# iot1.net
KiCad netlist of a schematic drawn in EAGLE
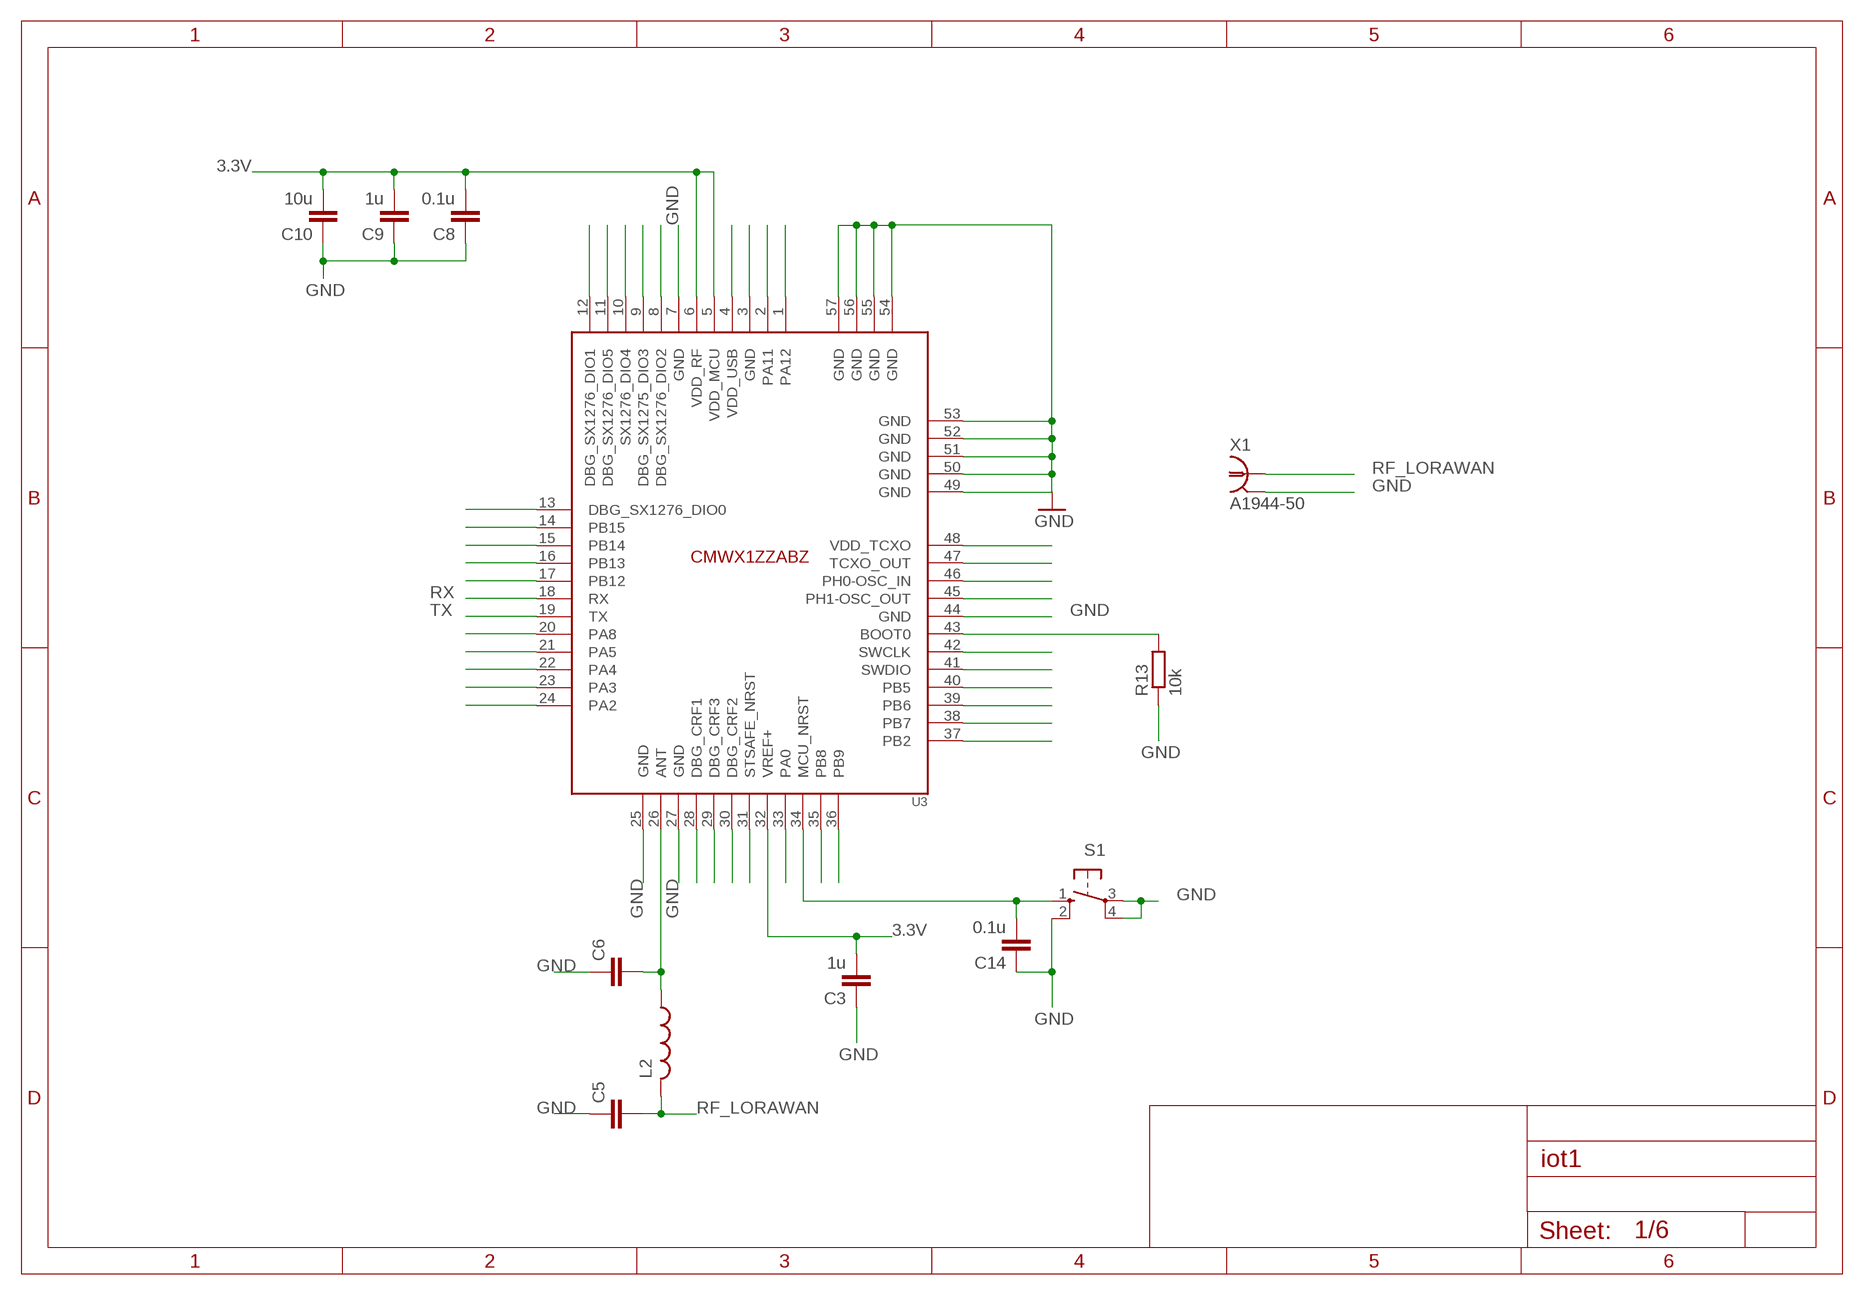
[diagram p0: schematic, sheet 1]
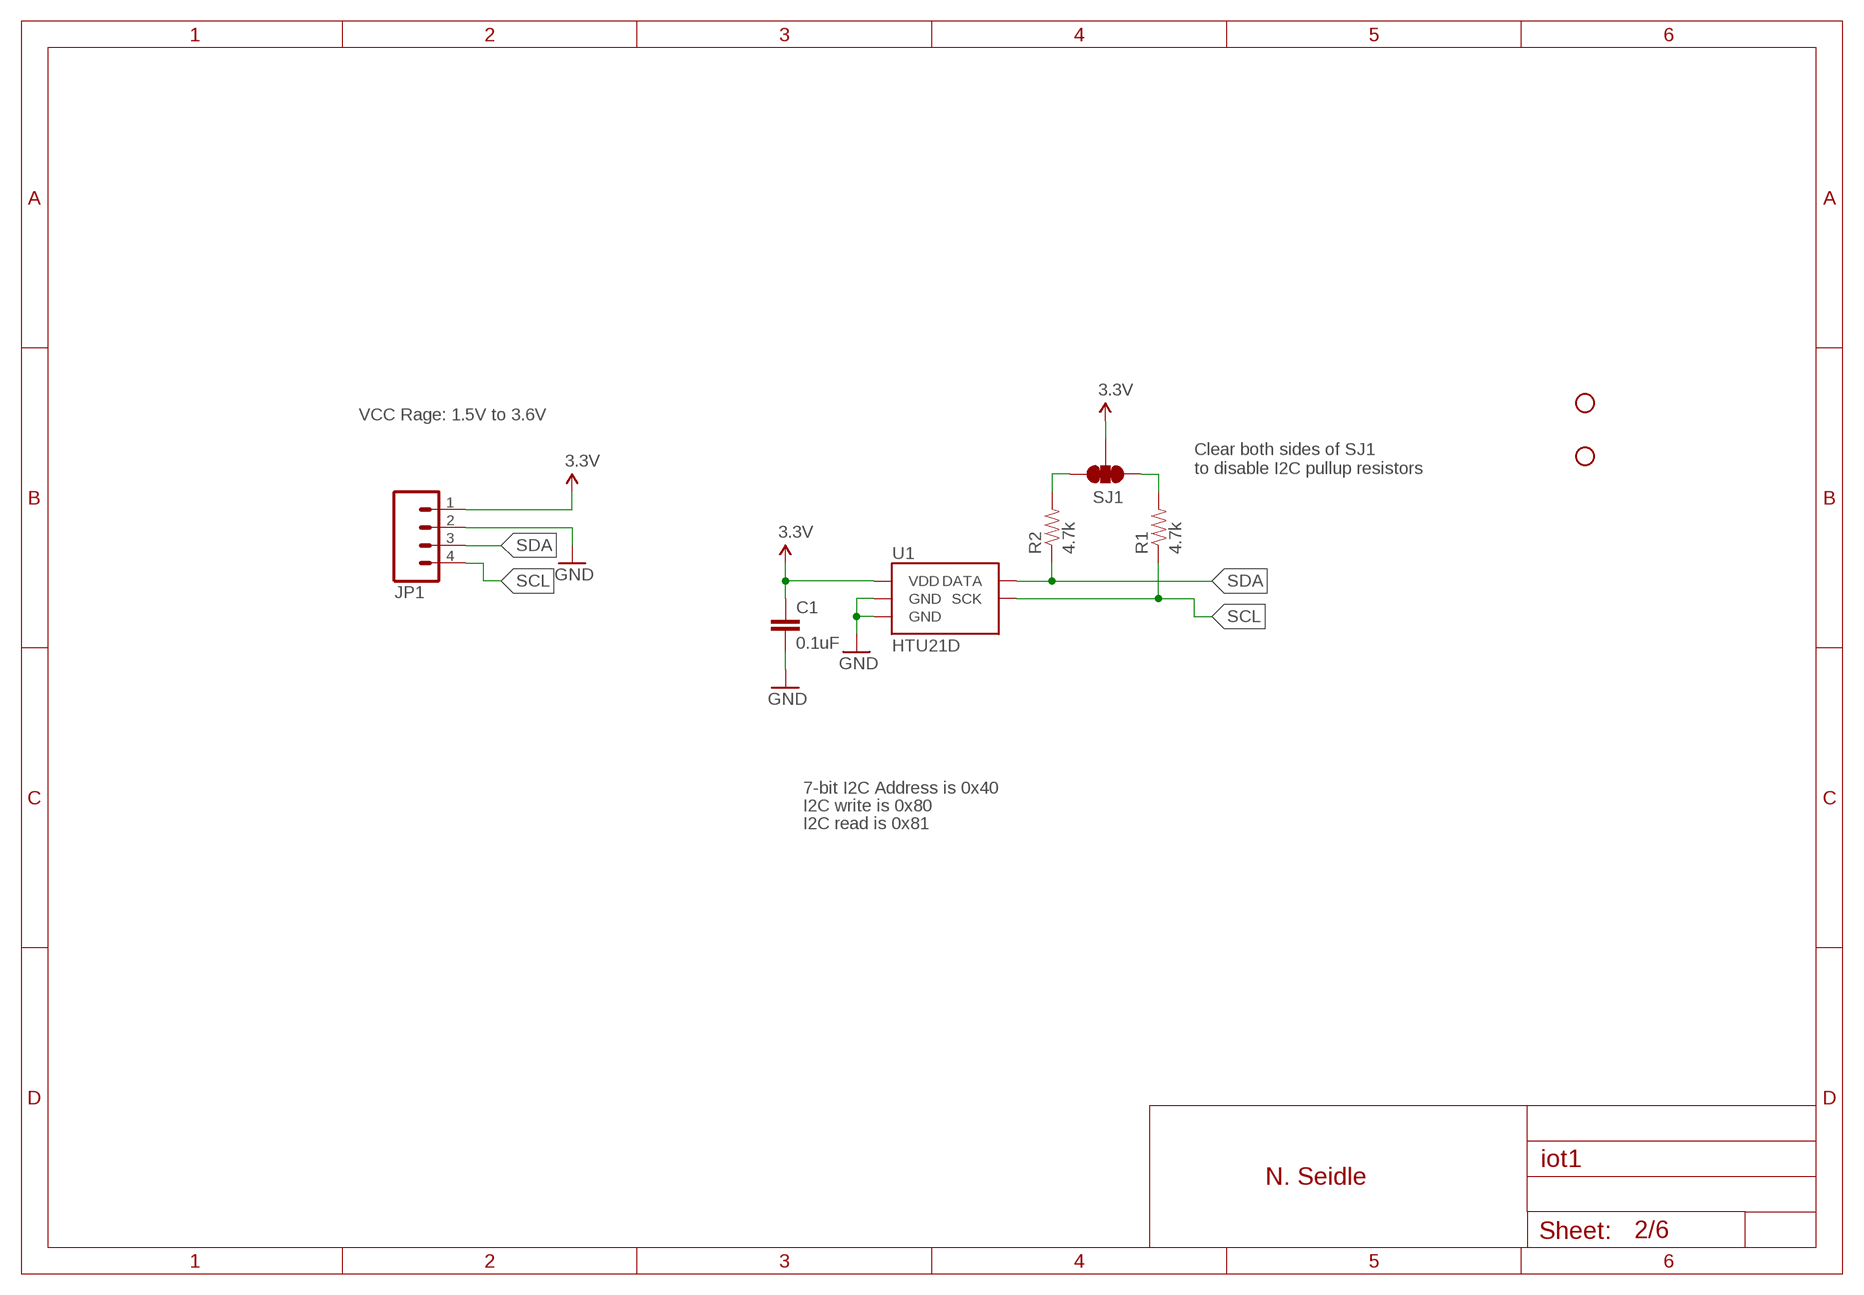
[diagram p1: schematic, sheet 2]
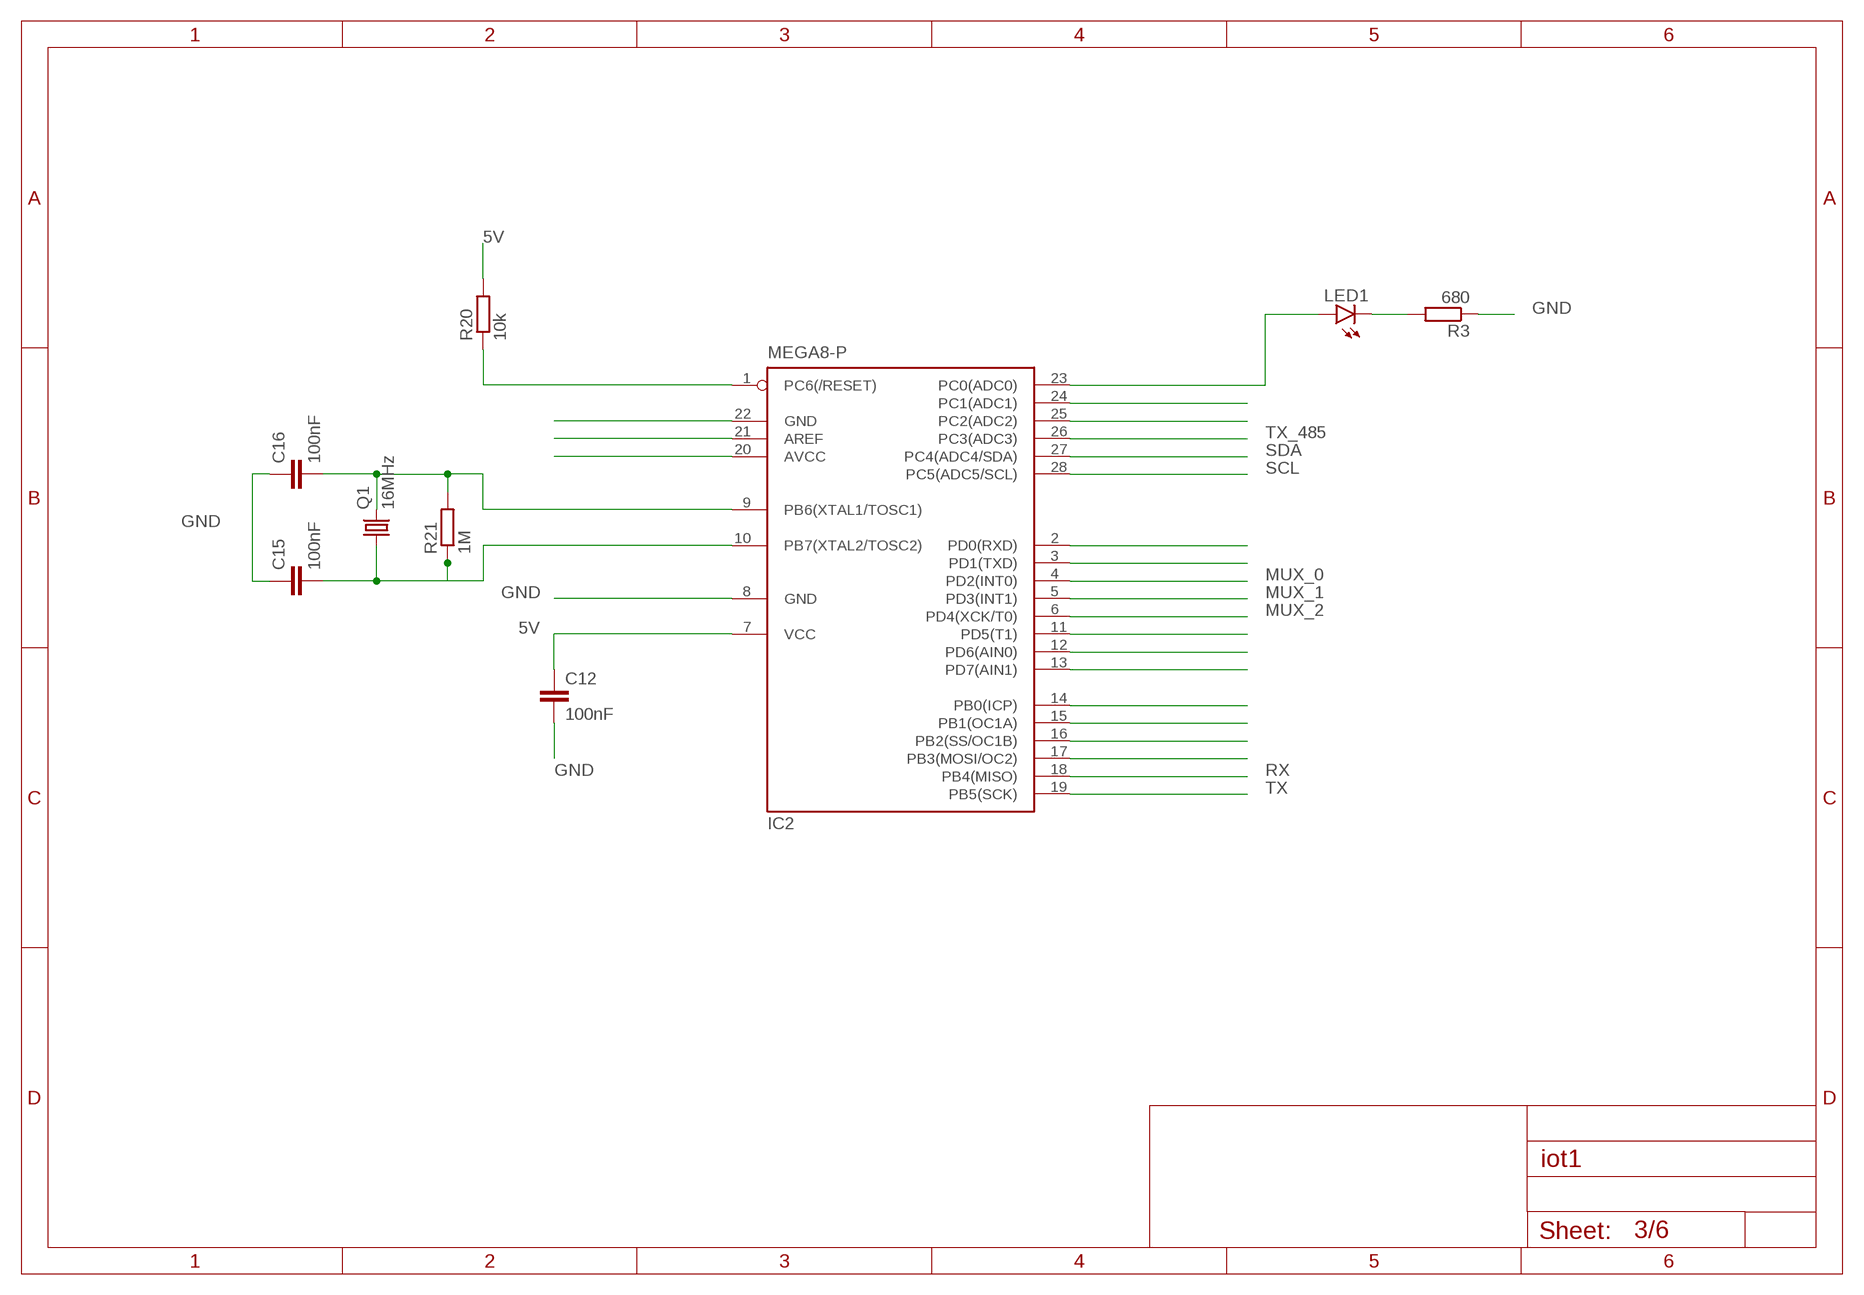
[diagram p2: schematic, sheet 3]
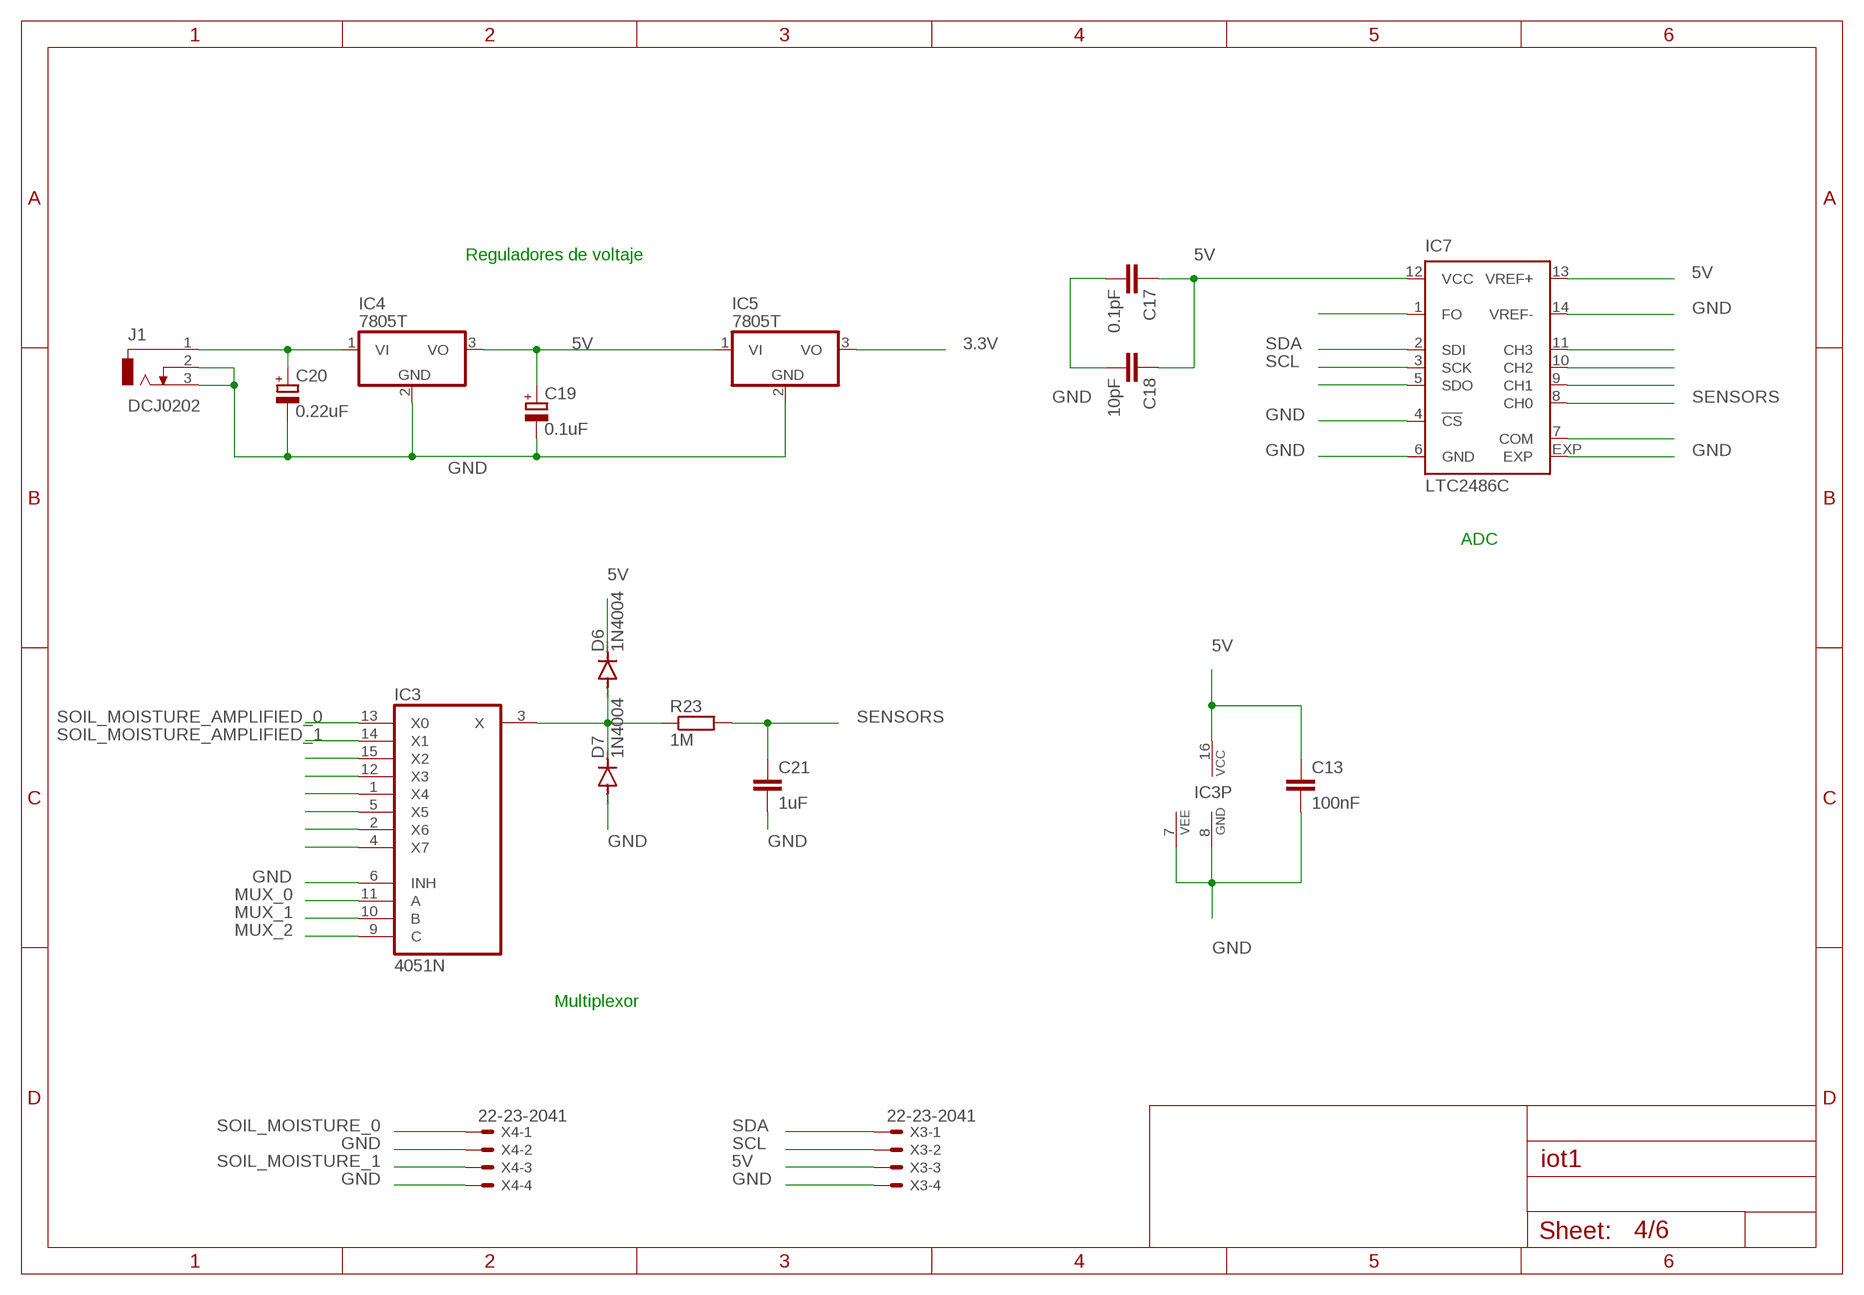
[diagram p3: schematic, sheet 4]
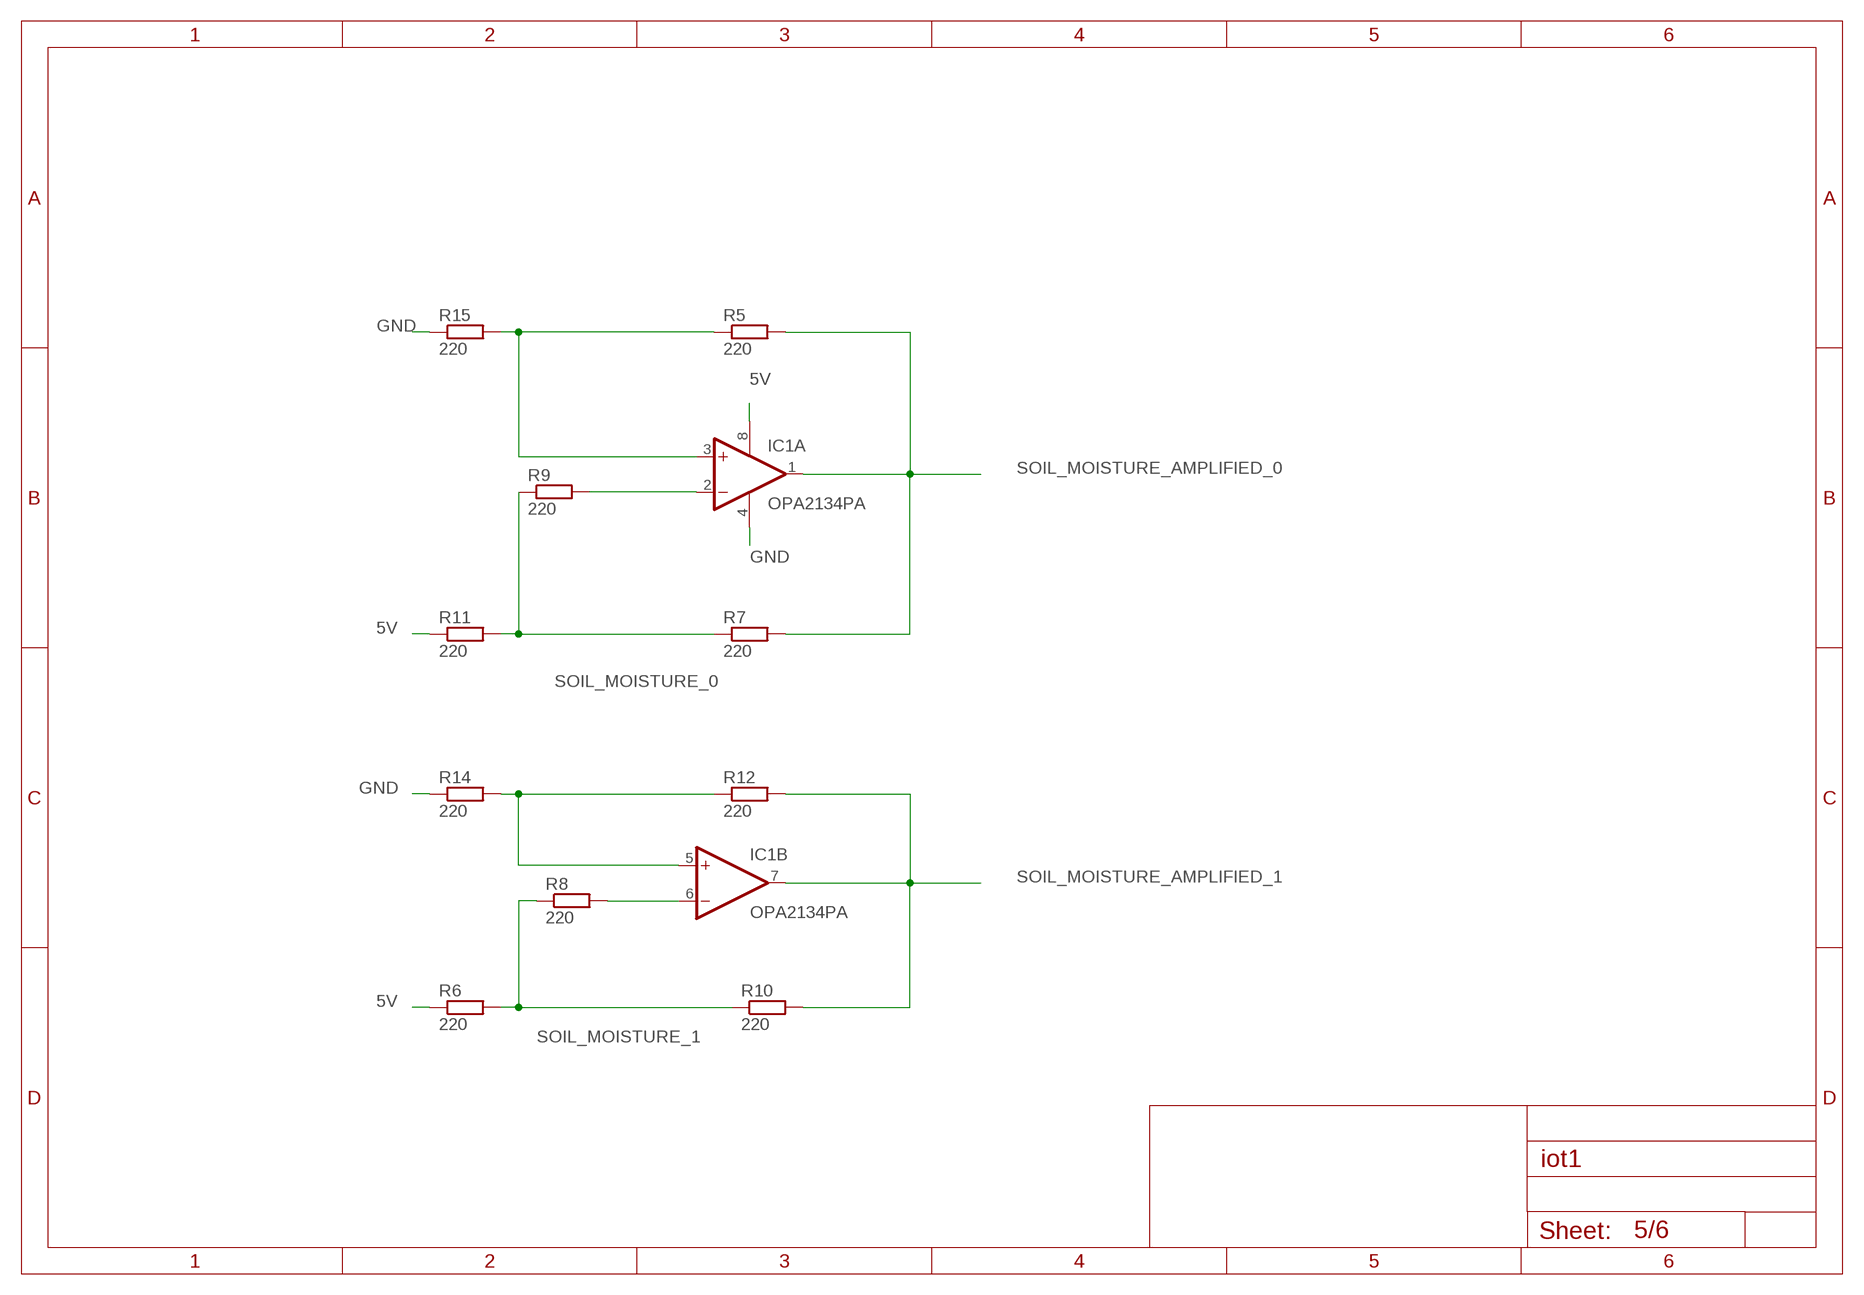
[diagram p4: schematic, sheet 5]
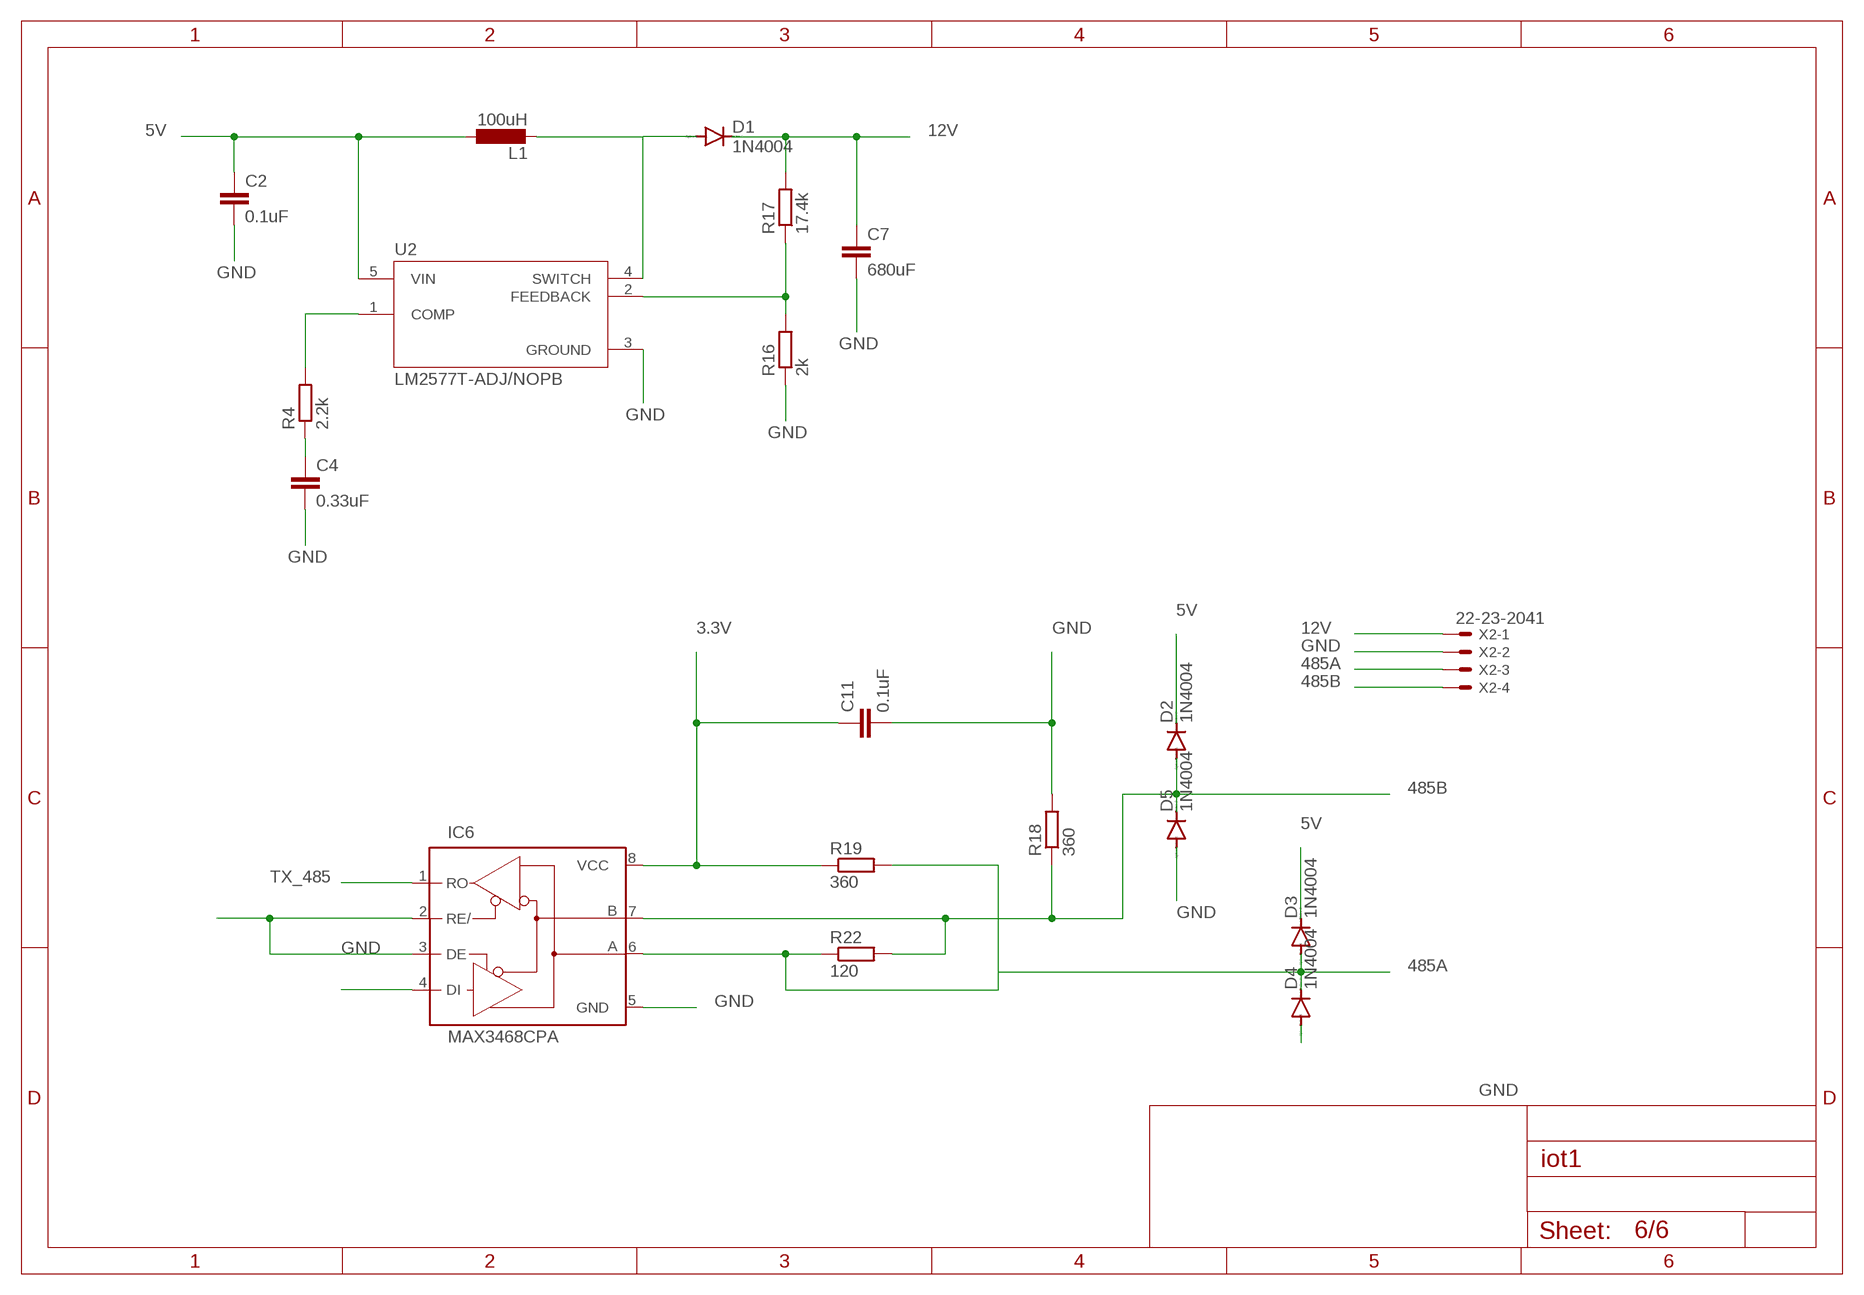
[diagram p5: schematic, sheet 6]

(export (version "E")
  (design (tool "Eeschema 10.0.6"))
  (components
    (comp (ref "C2")
      (value "0.1uF")
      (footprint "eagle-import:C025-024X044")
      (libsource (lib "eagle-import") (part "C-EU025-024X044"))
    )
    (comp (ref "C4")
      (value "0.33uF")
      (footprint "eagle-import:C025-024X044")
      (libsource (lib "eagle-import") (part "C-EU025-024X044"))
    )
    (comp (ref "C7")
      (value "680uF")
      (footprint "eagle-import:C025-024X044")
      (libsource (lib "eagle-import") (part "C-EU025-024X044"))
    )
    (comp (ref "C11")
      (value "0.1uF")
      (footprint "eagle-import:C025-024X044")
      (libsource (lib "eagle-import") (part "C-EU025-024X044"))
    )
    (comp (ref "D1")
      (value "1N4004")
      (footprint "eagle-import:DO41-10")
      (libsource (lib "eagle-import") (part "1N4004"))
    )
    (comp (ref "D2")
      (value "1N4004")
      (footprint "eagle-import:DO41-10")
      (libsource (lib "eagle-import") (part "1N4004"))
    )
    (comp (ref "D3")
      (value "1N4004")
      (footprint "eagle-import:DO41-10")
      (libsource (lib "eagle-import") (part "1N4004"))
    )
    (comp (ref "D4")
      (value "1N4004")
      (footprint "eagle-import:DO41-10")
      (libsource (lib "eagle-import") (part "1N4004"))
    )
    (comp (ref "D5")
      (value "1N4004")
      (footprint "eagle-import:DO41-10")
      (libsource (lib "eagle-import") (part "1N4004"))
    )
    (comp (ref "IC6")
      (value "MAX3468CPA")
      (footprint "eagle-import:DIL08")
      (libsource (lib "eagle-import") (part "MAX34PA68C"))
    )
    (comp (ref "L1")
      (value "100uH")
      (footprint "eagle-import:L1812")
      (libsource (lib "eagle-import") (part "L-EUL1812"))
    )
    (comp (ref "R4")
      (value "2.2k")
      (footprint "eagle-import:0204_7")
      (libsource (lib "eagle-import") (part "R-EU_0204/7"))
    )
    (comp (ref "R16")
      (value "2k")
      (footprint "eagle-import:0204_7")
      (libsource (lib "eagle-import") (part "R-EU_0204/7"))
    )
    (comp (ref "R17")
      (value "17.4k")
      (footprint "eagle-import:0204_7")
      (libsource (lib "eagle-import") (part "R-EU_0204/7"))
    )
    (comp (ref "R18")
      (value "360")
      (footprint "eagle-import:0207_10")
      (libsource (lib "eagle-import") (part "R-EU_0207/10"))
    )
    (comp (ref "R19")
      (value "360")
      (footprint "eagle-import:0207_10")
      (libsource (lib "eagle-import") (part "R-EU_0207/10"))
    )
    (comp (ref "R22")
      (value "120")
      (footprint "eagle-import:0207_10")
      (libsource (lib "eagle-import") (part "R-EU_0207/10"))
    )
    (comp (ref "U2")
      (value "LM2577T-ADJ/NOPB")
      (footprint "eagle-import:VREG_LM2577T-ADJ_NOPB")
      (fields (field (name "MF") "Texas Instruments") (field (name "MP") "LM2577T-ADJ"))
      (libsource (lib "eagle-import") (part "LM2577T-ADJ/NOPB"))
    )
    (comp (ref "X2")
      (value "22-23-2041")
      (footprint "eagle-import:22-23-2041")
      (fields (field (name "MF") "MOLEX"))
      (libsource (lib "eagle-import") (part "22-23-2041"))
    )
    (comp (ref "C1")
      (value "0.1uF")
      (footprint "eagle-import:0603-CAP")
      (libsource (lib "eagle-import") (part "CAP0603-CAP"))
    )
    (comp (ref "JP1")
      (value "M04PTH")
      (footprint "eagle-import:1X04")
      (libsource (lib "eagle-import") (part "M04PTH"))
    )
    (comp (ref "R1")
      (value "4.7k")
      (footprint "eagle-import:0603-RES")
      (libsource (lib "eagle-import") (part "RESISTOR0603-RES"))
    )
    (comp (ref "R2")
      (value "4.7k")
      (footprint "eagle-import:0603-RES")
      (libsource (lib "eagle-import") (part "RESISTOR0603-RES"))
    )
    (comp (ref "SJ1")
      (value "SOLDERJUMPER_2WAYPASTE1&2&3")
      (footprint "eagle-import:SJ_3_PASTE1&2&3")
      (libsource (lib "eagle-import") (part "SOLDERJUMPER_2WAYPASTE1&2&3"))
    )
    (comp (ref "STANDOFF1")
      (value "STAND-OFF")
      (footprint "eagle-import:STAND-OFF")
      (libsource (lib "eagle-import") (part "STAND-OFF"))
    )
    (comp (ref "STANDOFF3")
      (value "STAND-OFF")
      (footprint "eagle-import:STAND-OFF")
      (libsource (lib "eagle-import") (part "STAND-OFF"))
    )
    (comp (ref "U1")
      (value "HTU21D")
      (footprint "eagle-import:HTU21D")
      (libsource (lib "eagle-import") (part "HTU21DSMD"))
    )
    (comp (ref "C13")
      (value "100nF")
      (footprint "eagle-import:C0603")
      (libsource (lib "eagle-import") (part "C-EUC0603"))
    )
    (comp (ref "C17")
      (value "0.1pF")
      (footprint "eagle-import:C0603")
      (libsource (lib "eagle-import") (part "C-EUC0603"))
    )
    (comp (ref "C18")
      (value "10pF")
      (footprint "eagle-import:C0603")
      (libsource (lib "eagle-import") (part "C-EUC0603"))
    )
    (comp (ref "C19")
      (value "0.1uF")
      (footprint "eagle-import:E1,8-4")
      (libsource (lib "eagle-import") (part "CPOL-EUE1.8-4"))
    )
    (comp (ref "C20")
      (value "0.22uF")
      (footprint "eagle-import:E1,8-4")
      (libsource (lib "eagle-import") (part "CPOL-EUE1.8-4"))
    )
    (comp (ref "C21")
      (value "1uF")
      (footprint "eagle-import:C0603")
      (libsource (lib "eagle-import") (part "C-EUC0603"))
    )
    (comp (ref "D6")
      (value "1N4004")
      (footprint "eagle-import:DO41-10")
      (libsource (lib "eagle-import") (part "1N4004"))
    )
    (comp (ref "D7")
      (value "1N4004")
      (footprint "eagle-import:DO41-10")
      (libsource (lib "eagle-import") (part "1N4004"))
    )
    (comp (ref "IC3")
      (value "4051N")
      (footprint "eagle-import:DIL16")
      (libsource (lib "eagle-import") (part "4051N"))
    )
    (comp (ref "IC4")
      (value "7805T")
      (footprint "eagle-import:TO220H")
      (libsource (lib "eagle-import") (part "78T05"))
    )
    (comp (ref "IC5")
      (value "7805T")
      (footprint "eagle-import:TO220H")
      (libsource (lib "eagle-import") (part "78T05"))
    )
    (comp (ref "IC7")
      (value "LTC2486C")
      (footprint "eagle-import:DFN14-4X3")
      (libsource (lib "eagle-import") (part "LTC2486C"))
    )
    (comp (ref "J1")
      (value "DCJ0202")
      (footprint "eagle-import:DCJ0202")
      (libsource (lib "eagle-import") (part "DCJ0202"))
    )
    (comp (ref "R23")
      (value "1M")
      (footprint "eagle-import:0207_10")
      (libsource (lib "eagle-import") (part "R-EU_0207/10"))
    )
    (comp (ref "X3")
      (value "22-23-2041")
      (footprint "eagle-import:22-23-2041")
      (fields (field (name "MF") "MOLEX"))
      (libsource (lib "eagle-import") (part "22-23-2041"))
    )
    (comp (ref "X4")
      (value "22-23-2041")
      (footprint "eagle-import:22-23-2041")
      (fields (field (name "MF") "MOLEX"))
      (libsource (lib "eagle-import") (part "22-23-2041"))
    )
    (comp (ref "C3")
      (value "1u")
      (footprint "eagle-import:C050-025X075")
      (libsource (lib "eagle-import") (part "C-EU050-025X075"))
    )
    (comp (ref "C5")
      (value "C-EU050-025X075")
      (footprint "eagle-import:C050-025X075")
      (libsource (lib "eagle-import") (part "C-EU050-025X075"))
    )
    (comp (ref "C6")
      (value "C-EU050-025X075")
      (footprint "eagle-import:C050-025X075")
      (libsource (lib "eagle-import") (part "C-EU050-025X075"))
    )
    (comp (ref "C8")
      (value "0.1u")
      (footprint "eagle-import:C050-025X075")
      (libsource (lib "eagle-import") (part "C-EU050-025X075"))
    )
    (comp (ref "C9")
      (value "1u")
      (footprint "eagle-import:C050-025X075")
      (libsource (lib "eagle-import") (part "C-EU050-025X075"))
    )
    (comp (ref "C10")
      (value "10u")
      (footprint "eagle-import:C050-025X075")
      (libsource (lib "eagle-import") (part "C-EU050-025X075"))
    )
    (comp (ref "C14")
      (value "0.1u")
      (footprint "eagle-import:C050-025X075")
      (libsource (lib "eagle-import") (part "C-EU050-025X075"))
    )
    (comp (ref "L2")
      (value "L-US0207/7")
      (footprint "eagle-import:0207_7")
      (libsource (lib "eagle-import") (part "L-US0207/7"))
    )
    (comp (ref "R13")
      (value "10k")
      (footprint "eagle-import:0204_5")
      (libsource (lib "eagle-import") (part "R-EU_0204/5"))
    )
    (comp (ref "S1")
      (value "10-XX")
      (footprint "eagle-import:B3F-10XX")
      (fields (field (name "MPN") "B3F-1000"))
      (libsource (lib "eagle-import") (part "10-XX"))
    )
    (comp (ref "U3")
      (value "CMWX1ZZABZ")
      (footprint "eagle-import:CMWX1ZZABZ")
      (libsource (lib "eagle-import") (part "CMWX1ZZABZ"))
    )
    (comp (ref "X1")
      (value "A1944-50")
      (footprint "eagle-import:A1944")
      (libsource (lib "eagle-import") (part "A1944-50"))
    )
    (comp (ref "C12")
      (value "100nF")
      (footprint "eagle-import:C050-025X075")
      (libsource (lib "eagle-import") (part "C-EU050-025X075"))
    )
    (comp (ref "C15")
      (value "100nF")
      (footprint "eagle-import:C050-025X075")
      (libsource (lib "eagle-import") (part "C-EU050-025X075"))
    )
    (comp (ref "C16")
      (value "100nF")
      (footprint "eagle-import:C050-025X075")
      (libsource (lib "eagle-import") (part "C-EU050-025X075"))
    )
    (comp (ref "IC2")
      (value "MEGA8-P")
      (footprint "eagle-import:DIL28-3")
      (libsource (lib "eagle-import") (part "MEGA8-P"))
    )
    (comp (ref "LED1")
      (value "LED3MM")
      (footprint "eagle-import:LED3MM")
      (libsource (lib "eagle-import") (part "LED3MM"))
    )
    (comp (ref "Q1")
      (value "16MHz")
      (footprint "eagle-import:HC18U-V")
      (libsource (lib "eagle-import") (part "CRYSTALHC18U-V"))
    )
    (comp (ref "R3")
      (value "680")
      (footprint "eagle-import:0207_10")
      (libsource (lib "eagle-import") (part "R-EU_0207/10"))
    )
    (comp (ref "R20")
      (value "10k")
      (footprint "eagle-import:0204_7")
      (libsource (lib "eagle-import") (part "R-EU_0204/7"))
    )
    (comp (ref "R21")
      (value "1M")
      (footprint "eagle-import:0204_7")
      (libsource (lib "eagle-import") (part "R-EU_0204/7"))
    )
    (comp (ref "IC1")
      (value "OPA2134PA")
      (footprint "eagle-import:DIL08")
      (libsource (lib "eagle-import") (part "OPA2PA134"))
    )
    (comp (ref "R5")
      (value "220")
      (footprint "eagle-import:0207_10")
      (libsource (lib "eagle-import") (part "R-EU_0207/10"))
    )
    (comp (ref "R6")
      (value "220")
      (footprint "eagle-import:0207_10")
      (libsource (lib "eagle-import") (part "R-EU_0207/10"))
    )
    (comp (ref "R7")
      (value "220")
      (footprint "eagle-import:0207_10")
      (libsource (lib "eagle-import") (part "R-EU_0207/10"))
    )
    (comp (ref "R8")
      (value "220")
      (footprint "eagle-import:0207_10")
      (libsource (lib "eagle-import") (part "R-EU_0207/10"))
    )
    (comp (ref "R9")
      (value "220")
      (footprint "eagle-import:0207_10")
      (libsource (lib "eagle-import") (part "R-EU_0207/10"))
    )
    (comp (ref "R10")
      (value "220")
      (footprint "eagle-import:0207_10")
      (libsource (lib "eagle-import") (part "R-EU_0207/10"))
    )
    (comp (ref "R11")
      (value "220")
      (footprint "eagle-import:0207_10")
      (libsource (lib "eagle-import") (part "R-EU_0207/10"))
    )
    (comp (ref "R12")
      (value "220")
      (footprint "eagle-import:0207_10")
      (libsource (lib "eagle-import") (part "R-EU_0207/10"))
    )
    (comp (ref "R14")
      (value "220")
      (footprint "eagle-import:0207_10")
      (libsource (lib "eagle-import") (part "R-EU_0207/10"))
    )
    (comp (ref "R15")
      (value "220")
      (footprint "eagle-import:0207_10")
      (libsource (lib "eagle-import") (part "R-EU_0207/10"))
    )
  )
  (nets
    (net (code "1") (name "3.3V") (class "Default")
      (node (ref "C1") (pin "1") (pinfunction "1_1") (pintype "passive"))
      (node (ref "C10") (pin "2") (pinfunction "2_2") (pintype "passive"))
      (node (ref "C11") (pin "1") (pinfunction "1_1") (pintype "passive"))
      (node (ref "C3") (pin "2") (pinfunction "2_2") (pintype "passive"))
      (node (ref "C8") (pin "2") (pinfunction "2_2") (pintype "passive"))
      (node (ref "C9") (pin "2") (pinfunction "2_2") (pintype "passive"))
      (node (ref "IC5") (pin "3") (pinfunction "VO_3") (pintype "passive"))
      (node (ref "IC6") (pin "8") (pinfunction "VCC_8") (pintype "power_in"))
      (node (ref "JP1") (pin "1") (pinfunction "1_1") (pintype "passive"))
      (node (ref "R19") (pin "1") (pinfunction "1_1") (pintype "passive"))
      (node (ref "SJ1") (pin "2") (pinfunction "2_2") (pintype "passive"))
      (node (ref "U1") (pin "VDD") (pinfunction "VDD_VDD") (pintype "power_in"))
      (node (ref "U3") (pin "32") (pinfunction "VREF+_32") (pintype "bidirectional"))
      (node (ref "U3") (pin "5") (pinfunction "VDD_MCU_5") (pintype "bidirectional"))
      (node (ref "U3") (pin "6") (pinfunction "VDD_RF_6") (pintype "bidirectional"))
    )
    (net (code "2") (name "5V") (class "Default")
      (node (ref "C12") (pin "1") (pinfunction "1_1") (pintype "passive"))
      (node (ref "C13") (pin "1") (pinfunction "1_1") (pintype "passive"))
      (node (ref "C17") (pin "1") (pinfunction "1_1") (pintype "passive"))
      (node (ref "C18") (pin "1") (pinfunction "1_1") (pintype "passive"))
      (node (ref "C19") (pin "+") (pinfunction "+_+") (pintype "passive"))
      (node (ref "C2") (pin "1") (pinfunction "1_1") (pintype "passive"))
      (node (ref "D2") (pin "C") (pinfunction "C_C") (pintype "passive"))
      (node (ref "D3") (pin "C") (pinfunction "C_C") (pintype "passive"))
      (node (ref "D6") (pin "C") (pinfunction "C_C") (pintype "passive"))
      (node (ref "IC1") (pin "8") (pinfunction "V+_8") (pintype "power_in"))
      (node (ref "IC2") (pin "7") (pinfunction "VCC_7") (pintype "power_in"))
      (node (ref "IC3") (pin "16") (pinfunction "VCC_16") (pintype "power_in"))
      (node (ref "IC4") (pin "3") (pinfunction "VO_3") (pintype "passive"))
      (node (ref "IC5") (pin "1") (pinfunction "VI_1") (pintype "input"))
      (node (ref "IC7") (pin "12") (pinfunction "VCC_12") (pintype "power_in"))
      (node (ref "IC7") (pin "13") (pinfunction "VREF+_13") (pintype "input"))
      (node (ref "L1") (pin "1") (pinfunction "1_1") (pintype "passive"))
      (node (ref "R11") (pin "1") (pinfunction "1_1") (pintype "passive"))
      (node (ref "R20") (pin "2") (pinfunction "2_2") (pintype "passive"))
      (node (ref "R6") (pin "1") (pinfunction "1_1") (pintype "passive"))
      (node (ref "U2") (pin "5") (pinfunction "VIN_5") (pintype "input"))
      (node (ref "X3") (pin "3") (pinfunction "S_3") (pintype "passive"))
    )
    (net (code "3") (name "12V") (class "Default")
      (node (ref "C7") (pin "1") (pinfunction "1_1") (pintype "passive"))
      (node (ref "D1") (pin "C") (pinfunction "C_C") (pintype "passive"))
      (node (ref "R17") (pin "2") (pinfunction "2_2") (pintype "passive"))
      (node (ref "X2") (pin "1") (pinfunction "S_1") (pintype "passive"))
    )
    (net (code "4") (name "485A") (class "Default")
      (node (ref "D3") (pin "A") (pinfunction "A_A") (pintype "passive"))
      (node (ref "D4") (pin "C") (pinfunction "C_C") (pintype "passive"))
      (node (ref "IC6") (pin "6") (pinfunction "A_6") (pintype "passive"))
      (node (ref "R19") (pin "2") (pinfunction "2_2") (pintype "passive"))
      (node (ref "R22") (pin "1") (pinfunction "1_1") (pintype "passive"))
      (node (ref "X2") (pin "3") (pinfunction "S_3") (pintype "passive"))
    )
    (net (code "5") (name "485B") (class "Default")
      (node (ref "D2") (pin "A") (pinfunction "A_A") (pintype "passive"))
      (node (ref "D5") (pin "C") (pinfunction "C_C") (pintype "passive"))
      (node (ref "IC6") (pin "7") (pinfunction "B_7") (pintype "passive"))
      (node (ref "R18") (pin "1") (pinfunction "1_1") (pintype "passive"))
      (node (ref "R22") (pin "2") (pinfunction "2_2") (pintype "passive"))
      (node (ref "X2") (pin "4") (pinfunction "S_4") (pintype "passive"))
    )
    (net (code "6") (name "GND") (class "Default")
      (node (ref "C1") (pin "2") (pinfunction "2_2") (pintype "passive"))
      (node (ref "C10") (pin "1") (pinfunction "1_1") (pintype "passive"))
      (node (ref "C11") (pin "2") (pinfunction "2_2") (pintype "passive"))
      (node (ref "C12") (pin "2") (pinfunction "2_2") (pintype "passive"))
      (node (ref "C13") (pin "2") (pinfunction "2_2") (pintype "passive"))
      (node (ref "C14") (pin "1") (pinfunction "1_1") (pintype "passive"))
      (node (ref "C15") (pin "1") (pinfunction "1_1") (pintype "passive"))
      (node (ref "C16") (pin "1") (pinfunction "1_1") (pintype "passive"))
      (node (ref "C17") (pin "2") (pinfunction "2_2") (pintype "passive"))
      (node (ref "C18") (pin "2") (pinfunction "2_2") (pintype "passive"))
      (node (ref "C19") (pin "-") (pinfunction "-_-") (pintype "passive"))
      (node (ref "C2") (pin "2") (pinfunction "2_2") (pintype "passive"))
      (node (ref "C20") (pin "-") (pinfunction "-_-") (pintype "passive"))
      (node (ref "C21") (pin "2") (pinfunction "2_2") (pintype "passive"))
      (node (ref "C3") (pin "1") (pinfunction "1_1") (pintype "passive"))
      (node (ref "C4") (pin "2") (pinfunction "2_2") (pintype "passive"))
      (node (ref "C5") (pin "1") (pinfunction "1_1") (pintype "passive"))
      (node (ref "C6") (pin "1") (pinfunction "1_1") (pintype "passive"))
      (node (ref "C7") (pin "2") (pinfunction "2_2") (pintype "passive"))
      (node (ref "C8") (pin "1") (pinfunction "1_1") (pintype "passive"))
      (node (ref "C9") (pin "1") (pinfunction "1_1") (pintype "passive"))
      (node (ref "D4") (pin "A") (pinfunction "A_A") (pintype "passive"))
      (node (ref "D5") (pin "A") (pinfunction "A_A") (pintype "passive"))
      (node (ref "D7") (pin "A") (pinfunction "A_A") (pintype "passive"))
      (node (ref "IC1") (pin "4") (pinfunction "V-_4") (pintype "power_in"))
      (node (ref "IC2") (pin "8") (pinfunction "GND_8") (pintype "power_in"))
      (node (ref "IC3") (pin "6") (pinfunction "INH_6") (pintype "input"))
      (node (ref "IC3") (pin "7") (pinfunction "VEE_7") (pintype "power_in"))
      (node (ref "IC3") (pin "8") (pinfunction "GND_8") (pintype "power_in"))
      (node (ref "IC4") (pin "2") (pinfunction "GND_2") (pintype "passive"))
      (node (ref "IC5") (pin "2") (pinfunction "GND_2") (pintype "passive"))
      (node (ref "IC6") (pin "2") (pinfunction "RE/_2") (pintype "input"))
      (node (ref "IC6") (pin "3") (pinfunction "DE_3") (pintype "input"))
      (node (ref "IC6") (pin "5") (pinfunction "GND_5") (pintype "power_in"))
      (node (ref "IC7") (pin "14") (pinfunction "VREF-_14") (pintype "input"))
      (node (ref "IC7") (pin "4") (pinfunction "~{CS}_4") (pintype "input"))
      (node (ref "IC7") (pin "6") (pinfunction "GND_6") (pintype "power_in"))
      (node (ref "IC7") (pin "EXP") (pinfunction "EXP_EXP") (pintype "input"))
      (node (ref "J1") (pin "2") (pinfunction "2_2") (pintype "passive"))
      (node (ref "J1") (pin "3") (pinfunction "3_3") (pintype "passive"))
      (node (ref "JP1") (pin "2") (pinfunction "2_2") (pintype "passive"))
      (node (ref "R13") (pin "1") (pinfunction "1_1") (pintype "passive"))
      (node (ref "R14") (pin "1") (pinfunction "1_1") (pintype "passive"))
      (node (ref "R15") (pin "1") (pinfunction "1_1") (pintype "passive"))
      (node (ref "R16") (pin "1") (pinfunction "1_1") (pintype "passive"))
      (node (ref "R18") (pin "2") (pinfunction "2_2") (pintype "passive"))
      (node (ref "R3") (pin "1") (pinfunction "1_1") (pintype "passive"))
      (node (ref "S1") (pin "2") (pinfunction "S1_2") (pintype "passive"))
      (node (ref "S1") (pin "3") (pinfunction "P_3") (pintype "passive"))
      (node (ref "S1") (pin "4") (pinfunction "P1_4") (pintype "passive"))
      (node (ref "U1") (pin "7") (pinfunction "GND_7") (pintype "power_in"))
      (node (ref "U1") (pin "GND") (pinfunction "GND_GND") (pintype "power_in"))
      (node (ref "U2") (pin "3") (pinfunction "GROUND_3") (pintype "power_in"))
      (node (ref "U3") (pin "25") (pinfunction "GND_25") (pintype "bidirectional"))
      (node (ref "U3") (pin "27") (pinfunction "GND_27") (pintype "bidirectional"))
      (node (ref "U3") (pin "44") (pinfunction "GND_44") (pintype "bidirectional"))
      (node (ref "U3") (pin "49") (pinfunction "GND_49") (pintype "bidirectional"))
      (node (ref "U3") (pin "50") (pinfunction "GND_50") (pintype "bidirectional"))
      (node (ref "U3") (pin "51") (pinfunction "GND_51") (pintype "bidirectional"))
      (node (ref "U3") (pin "52") (pinfunction "GND_52") (pintype "bidirectional"))
      (node (ref "U3") (pin "53") (pinfunction "GND_53") (pintype "bidirectional"))
      (node (ref "U3") (pin "54") (pinfunction "GND_54") (pintype "bidirectional"))
      (node (ref "U3") (pin "55") (pinfunction "GND_55") (pintype "bidirectional"))
      (node (ref "U3") (pin "56") (pinfunction "GND_56") (pintype "bidirectional"))
      (node (ref "U3") (pin "57") (pinfunction "GND_57") (pintype "bidirectional"))
      (node (ref "U3") (pin "7") (pinfunction "GND_7") (pintype "bidirectional"))
      (node (ref "X1") (pin "2") (pinfunction "2_2") (pintype "passive"))
      (node (ref "X1") (pin "3") (pinfunction "2_3") (pintype "passive"))
      (node (ref "X1") (pin "4") (pinfunction "2_4") (pintype "passive"))
      (node (ref "X1") (pin "5") (pinfunction "2_5") (pintype "passive"))
      (node (ref "X2") (pin "2") (pinfunction "S_2") (pintype "passive"))
      (node (ref "X3") (pin "4") (pinfunction "S_4") (pintype "passive"))
      (node (ref "X4") (pin "2") (pinfunction "S_2") (pintype "passive"))
      (node (ref "X4") (pin "4") (pinfunction "S_4") (pintype "passive"))
    )
    (net (code "7") (name "MUX_0") (class "Default")
      (node (ref "IC2") (pin "4") (pinfunction "PD2(INT0)_4") (pintype "bidirectional"))
      (node (ref "IC3") (pin "11") (pinfunction "A_11") (pintype "input"))
    )
    (net (code "8") (name "MUX_1") (class "Default")
      (node (ref "IC2") (pin "5") (pinfunction "PD3(INT1)_5") (pintype "bidirectional"))
      (node (ref "IC3") (pin "10") (pinfunction "B_10") (pintype "input"))
    )
    (net (code "9") (name "MUX_2") (class "Default")
      (node (ref "IC2") (pin "6") (pinfunction "PD4(XCK/T0)_6") (pintype "bidirectional"))
      (node (ref "IC3") (pin "9") (pinfunction "C_9") (pintype "input"))
    )
    (net (code "10") (name "Net-(C4-Pad1)") (class "Default")
      (node (ref "C4") (pin "1") (pinfunction "1_1") (pintype "passive"))
      (node (ref "R4") (pin "1") (pinfunction "1_1") (pintype "passive"))
    )
    (net (code "11") (name "Net-(IC1A-+IN)") (class "Default")
      (node (ref "IC1") (pin "3") (pinfunction "+IN_3") (pintype "input"))
      (node (ref "R15") (pin "2") (pinfunction "2_2") (pintype "passive"))
      (node (ref "R5") (pin "1") (pinfunction "1_1") (pintype "passive"))
    )
    (net (code "12") (name "Net-(IC1A--IN)") (class "Default")
      (node (ref "IC1") (pin "2") (pinfunction "-IN_2") (pintype "input"))
      (node (ref "R9") (pin "2") (pinfunction "2_2") (pintype "passive"))
    )
    (net (code "13") (name "Net-(IC1B-+IN)") (class "Default")
      (node (ref "IC1") (pin "5") (pinfunction "+IN_5") (pintype "input"))
      (node (ref "R12") (pin "1") (pinfunction "1_1") (pintype "passive"))
      (node (ref "R14") (pin "2") (pinfunction "2_2") (pintype "passive"))
    )
    (net (code "14") (name "Net-(IC1B--IN)") (class "Default")
      (node (ref "IC1") (pin "6") (pinfunction "-IN_6") (pintype "input"))
      (node (ref "R8") (pin "2") (pinfunction "2_2") (pintype "passive"))
    )
    (net (code "15") (name "Net-(IC2-PB6(XTAL1{slash}TOSC1))") (class "Default")
      (node (ref "C16") (pin "2") (pinfunction "2_2") (pintype "passive"))
      (node (ref "IC2") (pin "9") (pinfunction "PB6(XTAL1/TOSC1)_9") (pintype "bidirectional"))
      (node (ref "Q1") (pin "2") (pinfunction "2_2") (pintype "passive"))
      (node (ref "R21") (pin "2") (pinfunction "2_2") (pintype "passive"))
    )
    (net (code "16") (name "Net-(IC2-PB7(XTAL2{slash}TOSC2))") (class "Default")
      (node (ref "C15") (pin "2") (pinfunction "2_2") (pintype "passive"))
      (node (ref "IC2") (pin "10") (pinfunction "PB7(XTAL2/TOSC2)_10") (pintype "bidirectional"))
      (node (ref "Q1") (pin "1") (pinfunction "1_1") (pintype "passive"))
      (node (ref "R21") (pin "1") (pinfunction "1_1") (pintype "passive"))
    )
    (net (code "17") (name "Net-(IC2-PC0(ADC0))") (class "Default")
      (node (ref "IC2") (pin "23") (pinfunction "PC0(ADC0)_23") (pintype "bidirectional"))
      (node (ref "LED1") (pin "A") (pinfunction "A_A") (pintype "passive"))
    )
    (net (code "18") (name "Net-(IC2-PC6({slash}RESET))") (class "Default")
      (node (ref "IC2") (pin "1") (pinfunction "PC6(/RESET)_1") (pintype "bidirectional"))
      (node (ref "R20") (pin "1") (pinfunction "1_1") (pintype "passive"))
    )
    (net (code "19") (name "Net-(IC3A-X)") (class "Default")
      (node (ref "D6") (pin "A") (pinfunction "A_A") (pintype "passive"))
      (node (ref "D7") (pin "C") (pinfunction "C_C") (pintype "passive"))
      (node (ref "IC3") (pin "3") (pinfunction "X_3") (pintype "bidirectional"))
      (node (ref "R23") (pin "1") (pinfunction "1_1") (pintype "passive"))
    )
    (net (code "20") (name "Net-(IC4-VI)") (class "Default")
      (node (ref "C20") (pin "+") (pinfunction "+_+") (pintype "passive"))
      (node (ref "IC4") (pin "1") (pinfunction "VI_1") (pintype "input"))
      (node (ref "J1") (pin "1") (pinfunction "1_1") (pintype "passive"))
    )
    (net (code "21") (name "Net-(LED1-C)") (class "Default")
      (node (ref "LED1") (pin "K") (pinfunction "C_K") (pintype "passive"))
      (node (ref "R3") (pin "2") (pinfunction "2_2") (pintype "passive"))
    )
    (net (code "22") (name "Net-(R1-Pad2)") (class "Default")
      (node (ref "R1") (pin "2") (pinfunction "2_2") (pintype "passive"))
      (node (ref "SJ1") (pin "1") (pinfunction "1_1") (pintype "passive"))
    )
    (net (code "23") (name "Net-(R2-Pad2)") (class "Default")
      (node (ref "R2") (pin "2") (pinfunction "2_2") (pintype "passive"))
      (node (ref "SJ1") (pin "3") (pinfunction "3_3") (pintype "passive"))
    )
    (net (code "24") (name "Net-(S1-S)") (class "Default")
      (node (ref "C14") (pin "2") (pinfunction "2_2") (pintype "passive"))
      (node (ref "S1") (pin "1") (pinfunction "S_1") (pintype "passive"))
      (node (ref "U3") (pin "34") (pinfunction "MCU_NRST_34") (pintype "bidirectional"))
    )
    (net (code "25") (name "Net-(U2-COMP)") (class "Default")
      (node (ref "R4") (pin "2") (pinfunction "2_2") (pintype "passive"))
      (node (ref "U2") (pin "1") (pinfunction "COMP_1") (pintype "passive"))
    )
    (net (code "26") (name "Net-(U2-FEEDBACK)") (class "Default")
      (node (ref "R16") (pin "2") (pinfunction "2_2") (pintype "passive"))
      (node (ref "R17") (pin "1") (pinfunction "1_1") (pintype "passive"))
      (node (ref "U2") (pin "2") (pinfunction "FEEDBACK_2") (pintype "input"))
    )
    (net (code "27") (name "Net-(U2-SWITCH)") (class "Default")
      (node (ref "D1") (pin "A") (pinfunction "A_A") (pintype "passive"))
      (node (ref "L1") (pin "2") (pinfunction "2_2") (pintype "passive"))
      (node (ref "U2") (pin "4") (pinfunction "SWITCH_4") (pintype "output"))
    )
    (net (code "28") (name "Net-(U3-ANT)") (class "Default")
      (node (ref "C6") (pin "2") (pinfunction "2_2") (pintype "passive"))
      (node (ref "L2") (pin "1") (pinfunction "1_1") (pintype "passive"))
      (node (ref "U3") (pin "26") (pinfunction "ANT_26") (pintype "bidirectional"))
    )
    (net (code "29") (name "Net-(U3-BOOT0)") (class "Default")
      (node (ref "R13") (pin "2") (pinfunction "2_2") (pintype "passive"))
      (node (ref "U3") (pin "43") (pinfunction "BOOT0_43") (pintype "bidirectional"))
    )
    (net (code "30") (name "RF_LORAWAN") (class "Default")
      (node (ref "C5") (pin "2") (pinfunction "2_2") (pintype "passive"))
      (node (ref "L2") (pin "2") (pinfunction "2_2") (pintype "passive"))
      (node (ref "X1") (pin "1") (pinfunction "1_1") (pintype "passive"))
    )
    (net (code "31") (name "RX") (class "Default")
      (node (ref "IC2") (pin "18") (pinfunction "PB4(MISO)_18") (pintype "bidirectional"))
      (node (ref "U3") (pin "18") (pinfunction "RX_18") (pintype "bidirectional"))
    )
    (net (code "32") (name "SCL") (class "Default")
      (node (ref "IC2") (pin "28") (pinfunction "PC5(ADC5/SCL)_28") (pintype "bidirectional"))
      (node (ref "IC7") (pin "1") (pinfunction "FO_1") (pintype "input"))
      (node (ref "IC7") (pin "3") (pinfunction "SCK_3") (pintype "input"))
      (node (ref "JP1") (pin "4") (pinfunction "4_4") (pintype "passive"))
      (node (ref "R1") (pin "1") (pinfunction "1_1") (pintype "passive"))
      (node (ref "U1") (pin "SCK") (pinfunction "SCK_SCK") (pintype "input"))
      (node (ref "X3") (pin "2") (pinfunction "S_2") (pintype "passive"))
    )
    (net (code "33") (name "SDA") (class "Default")
      (node (ref "IC2") (pin "27") (pinfunction "PC4(ADC4/SDA)_27") (pintype "bidirectional"))
      (node (ref "IC7") (pin "2") (pinfunction "SDI_2") (pintype "input"))
      (node (ref "JP1") (pin "3") (pinfunction "3_3") (pintype "passive"))
      (node (ref "R2") (pin "1") (pinfunction "1_1") (pintype "passive"))
      (node (ref "U1") (pin "DATA") (pinfunction "DATA_DATA") (pintype "bidirectional"))
      (node (ref "X3") (pin "1") (pinfunction "S_1") (pintype "passive"))
    )
    (net (code "34") (name "SENSORS") (class "Default")
      (node (ref "C21") (pin "1") (pinfunction "1_1") (pintype "passive"))
      (node (ref "IC7") (pin "8") (pinfunction "CH0_8") (pintype "input"))
      (node (ref "R23") (pin "2") (pinfunction "2_2") (pintype "passive"))
    )
    (net (code "35") (name "SOIL_MOISTURE_0") (class "Default")
      (node (ref "R11") (pin "2") (pinfunction "2_2") (pintype "passive"))
      (node (ref "R7") (pin "1") (pinfunction "1_1") (pintype "passive"))
      (node (ref "R9") (pin "1") (pinfunction "1_1") (pintype "passive"))
      (node (ref "X4") (pin "1") (pinfunction "S_1") (pintype "passive"))
    )
    (net (code "36") (name "SOIL_MOISTURE_1") (class "Default")
      (node (ref "R10") (pin "1") (pinfunction "1_1") (pintype "passive"))
      (node (ref "R6") (pin "2") (pinfunction "2_2") (pintype "passive"))
      (node (ref "R8") (pin "1") (pinfunction "1_1") (pintype "passive"))
      (node (ref "X4") (pin "3") (pinfunction "S_3") (pintype "passive"))
    )
    (net (code "37") (name "SOIL_MOISTURE_AMPLIFIED_0") (class "Default")
      (node (ref "IC1") (pin "1") (pinfunction "OUT_1") (pintype "output"))
      (node (ref "IC3") (pin "13") (pinfunction "X0_13") (pintype "bidirectional"))
      (node (ref "R5") (pin "2") (pinfunction "2_2") (pintype "passive"))
      (node (ref "R7") (pin "2") (pinfunction "2_2") (pintype "passive"))
    )
    (net (code "38") (name "SOIL_MOISTURE_AMPLIFIED_1") (class "Default")
      (node (ref "IC1") (pin "7") (pinfunction "OUT_7") (pintype "output"))
      (node (ref "IC3") (pin "14") (pinfunction "X1_14") (pintype "bidirectional"))
      (node (ref "R10") (pin "2") (pinfunction "2_2") (pintype "passive"))
      (node (ref "R12") (pin "2") (pinfunction "2_2") (pintype "passive"))
    )
    (net (code "39") (name "TX") (class "Default")
      (node (ref "IC2") (pin "19") (pinfunction "PB5(SCK)_19") (pintype "bidirectional"))
      (node (ref "U3") (pin "19") (pinfunction "TX_19") (pintype "bidirectional"))
    )
    (net (code "40") (name "TX_485") (class "Default")
      (node (ref "IC2") (pin "26") (pinfunction "PC3(ADC3)_26") (pintype "bidirectional"))
      (node (ref "IC6") (pin "1") (pinfunction "RO_1") (pintype "output"))
    )
    (net (code "41") (name "unconnected-(IC2-AREF-Pad21)") (class "Default")
      (node (ref "IC2") (pin "21") (pinfunction "AREF_21") (pintype "passive"))
    )
    (net (code "42") (name "unconnected-(IC2-AVCC-Pad20)") (class "Default")
      (node (ref "IC2") (pin "20") (pinfunction "AVCC_20") (pintype "power_in"))
    )
    (net (code "43") (name "unconnected-(IC2-GND-Pad22)") (class "Default")
      (node (ref "IC2") (pin "22") (pinfunction "GND_22") (pintype "power_in"))
    )
    (net (code "44") (name "unconnected-(IC2-PB0(ICP)-Pad14)") (class "Default")
      (node (ref "IC2") (pin "14") (pinfunction "PB0(ICP)_14") (pintype "bidirectional"))
    )
    (net (code "45") (name "unconnected-(IC2-PB1(OC1A)-Pad15)") (class "Default")
      (node (ref "IC2") (pin "15") (pinfunction "PB1(OC1A)_15") (pintype "bidirectional"))
    )
    (net (code "46") (name "unconnected-(IC2-PB2(SS{slash}OC1B)-Pad16)") (class "Default")
      (node (ref "IC2") (pin "16") (pinfunction "PB2(SS/OC1B)_16") (pintype "bidirectional"))
    )
    (net (code "47") (name "unconnected-(IC2-PB3(MOSI{slash}OC2)-Pad17)") (class "Default")
      (node (ref "IC2") (pin "17") (pinfunction "PB3(MOSI/OC2)_17") (pintype "bidirectional"))
    )
    (net (code "48") (name "unconnected-(IC2-PC1(ADC1)-Pad24)") (class "Default")
      (node (ref "IC2") (pin "24") (pinfunction "PC1(ADC1)_24") (pintype "bidirectional"))
    )
    (net (code "49") (name "unconnected-(IC2-PC2(ADC2)-Pad25)") (class "Default")
      (node (ref "IC2") (pin "25") (pinfunction "PC2(ADC2)_25") (pintype "bidirectional"))
    )
    (net (code "50") (name "unconnected-(IC2-PD0(RXD)-Pad2)") (class "Default")
      (node (ref "IC2") (pin "2") (pinfunction "PD0(RXD)_2") (pintype "bidirectional"))
    )
    (net (code "51") (name "unconnected-(IC2-PD1(TXD)-Pad3)") (class "Default")
      (node (ref "IC2") (pin "3") (pinfunction "PD1(TXD)_3") (pintype "bidirectional"))
    )
    (net (code "52") (name "unconnected-(IC2-PD5(T1)-Pad11)") (class "Default")
      (node (ref "IC2") (pin "11") (pinfunction "PD5(T1)_11") (pintype "bidirectional"))
    )
    (net (code "53") (name "unconnected-(IC2-PD6(AIN0)-Pad12)") (class "Default")
      (node (ref "IC2") (pin "12") (pinfunction "PD6(AIN0)_12") (pintype "bidirectional"))
    )
    (net (code "54") (name "unconnected-(IC2-PD7(AIN1)-Pad13)") (class "Default")
      (node (ref "IC2") (pin "13") (pinfunction "PD7(AIN1)_13") (pintype "bidirectional"))
    )
    (net (code "55") (name "unconnected-(IC3A-X2-Pad15)") (class "Default")
      (node (ref "IC3") (pin "15") (pinfunction "X2_15") (pintype "bidirectional"))
    )
    (net (code "56") (name "unconnected-(IC3A-X3-Pad12)") (class "Default")
      (node (ref "IC3") (pin "12") (pinfunction "X3_12") (pintype "bidirectional"))
    )
    (net (code "57") (name "unconnected-(IC3A-X4-Pad1)") (class "Default")
      (node (ref "IC3") (pin "1") (pinfunction "X4_1") (pintype "bidirectional"))
    )
    (net (code "58") (name "unconnected-(IC3A-X5-Pad5)") (class "Default")
      (node (ref "IC3") (pin "5") (pinfunction "X5_5") (pintype "bidirectional"))
    )
    (net (code "59") (name "unconnected-(IC3A-X6-Pad2)") (class "Default")
      (node (ref "IC3") (pin "2") (pinfunction "X6_2") (pintype "bidirectional"))
    )
    (net (code "60") (name "unconnected-(IC3A-X7-Pad4)") (class "Default")
      (node (ref "IC3") (pin "4") (pinfunction "X7_4") (pintype "bidirectional"))
    )
    (net (code "61") (name "unconnected-(IC6-DI-Pad4)") (class "Default")
      (node (ref "IC6") (pin "4") (pinfunction "DI_4") (pintype "input"))
    )
    (net (code "62") (name "unconnected-(IC7-CH1-Pad9)") (class "Default")
      (node (ref "IC7") (pin "9") (pinfunction "CH1_9") (pintype "input"))
    )
    (net (code "63") (name "unconnected-(IC7-CH2-Pad10)") (class "Default")
      (node (ref "IC7") (pin "10") (pinfunction "CH2_10") (pintype "input"))
    )
    (net (code "64") (name "unconnected-(IC7-CH3-Pad11)") (class "Default")
      (node (ref "IC7") (pin "11") (pinfunction "CH3_11") (pintype "input"))
    )
    (net (code "65") (name "unconnected-(IC7-COM-Pad7)") (class "Default")
      (node (ref "IC7") (pin "7") (pinfunction "COM_7") (pintype "power_in"))
    )
    (net (code "66") (name "unconnected-(IC7-SDO-Pad5)") (class "Default")
      (node (ref "IC7") (pin "5") (pinfunction "SDO_5") (pintype "output"))
    )
    (net (code "67") (name "unconnected-(U3-DBG_CRF1-Pad28)") (class "Default")
      (node (ref "U3") (pin "28") (pinfunction "DBG_CRF1_28") (pintype "bidirectional"))
    )
    (net (code "68") (name "unconnected-(U3-DBG_CRF2-Pad30)") (class "Default")
      (node (ref "U3") (pin "30") (pinfunction "DBG_CRF2_30") (pintype "bidirectional"))
    )
    (net (code "69") (name "unconnected-(U3-DBG_CRF3-Pad29)") (class "Default")
      (node (ref "U3") (pin "29") (pinfunction "DBG_CRF3_29") (pintype "bidirectional"))
    )
    (net (code "70") (name "unconnected-(U3-DBG_SX1275_DIO3-Pad9)") (class "Default")
      (node (ref "U3") (pin "9") (pinfunction "DBG_SX1275_DIO3_9") (pintype "bidirectional"))
    )
    (net (code "71") (name "unconnected-(U3-DBG_SX1276_DIO0-Pad13)") (class "Default")
      (node (ref "U3") (pin "13") (pinfunction "DBG_SX1276_DIO0_13") (pintype "bidirectional"))
    )
    (net (code "72") (name "unconnected-(U3-DBG_SX1276_DIO1-Pad12)") (class "Default")
      (node (ref "U3") (pin "12") (pinfunction "DBG_SX1276_DIO1_12") (pintype "bidirectional"))
    )
    (net (code "73") (name "unconnected-(U3-DBG_SX1276_DIO2-Pad8)") (class "Default")
      (node (ref "U3") (pin "8") (pinfunction "DBG_SX1276_DIO2_8") (pintype "bidirectional"))
    )
    (net (code "74") (name "unconnected-(U3-DBG_SX1276_DIO5-Pad11)") (class "Default")
      (node (ref "U3") (pin "11") (pinfunction "DBG_SX1276_DIO5_11") (pintype "bidirectional"))
    )
    (net (code "75") (name "unconnected-(U3-GND-Pad3)") (class "Default")
      (node (ref "U3") (pin "3") (pinfunction "GND_3") (pintype "bidirectional"))
    )
    (net (code "76") (name "unconnected-(U3-PA0-Pad33)") (class "Default")
      (node (ref "U3") (pin "33") (pinfunction "PA0_33") (pintype "bidirectional"))
    )
    (net (code "77") (name "unconnected-(U3-PA2-Pad24)") (class "Default")
      (node (ref "U3") (pin "24") (pinfunction "PA2_24") (pintype "bidirectional"))
    )
    (net (code "78") (name "unconnected-(U3-PA3-Pad23)") (class "Default")
      (node (ref "U3") (pin "23") (pinfunction "PA3_23") (pintype "bidirectional"))
    )
    (net (code "79") (name "unconnected-(U3-PA4-Pad22)") (class "Default")
      (node (ref "U3") (pin "22") (pinfunction "PA4_22") (pintype "bidirectional"))
    )
    (net (code "80") (name "unconnected-(U3-PA5-Pad21)") (class "Default")
      (node (ref "U3") (pin "21") (pinfunction "PA5_21") (pintype "bidirectional"))
    )
    (net (code "81") (name "unconnected-(U3-PA8-Pad20)") (class "Default")
      (node (ref "U3") (pin "20") (pinfunction "PA8_20") (pintype "bidirectional"))
    )
    (net (code "82") (name "unconnected-(U3-PA11-Pad2)") (class "Default")
      (node (ref "U3") (pin "2") (pinfunction "PA11_2") (pintype "bidirectional"))
    )
    (net (code "83") (name "unconnected-(U3-PA12-Pad1)") (class "Default")
      (node (ref "U3") (pin "1") (pinfunction "PA12_1") (pintype "bidirectional"))
    )
    (net (code "84") (name "unconnected-(U3-PB2-Pad37)") (class "Default")
      (node (ref "U3") (pin "37") (pinfunction "PB2_37") (pintype "bidirectional"))
    )
    (net (code "85") (name "unconnected-(U3-PB5-Pad40)") (class "Default")
      (node (ref "U3") (pin "40") (pinfunction "PB5_40") (pintype "bidirectional"))
    )
    (net (code "86") (name "unconnected-(U3-PB6-Pad39)") (class "Default")
      (node (ref "U3") (pin "39") (pinfunction "PB6_39") (pintype "bidirectional"))
    )
    (net (code "87") (name "unconnected-(U3-PB7-Pad38)") (class "Default")
      (node (ref "U3") (pin "38") (pinfunction "PB7_38") (pintype "bidirectional"))
    )
    (net (code "88") (name "unconnected-(U3-PB8-Pad35)") (class "Default")
      (node (ref "U3") (pin "35") (pinfunction "PB8_35") (pintype "bidirectional"))
    )
    (net (code "89") (name "unconnected-(U3-PB9-Pad36)") (class "Default")
      (node (ref "U3") (pin "36") (pinfunction "PB9_36") (pintype "bidirectional"))
    )
    (net (code "90") (name "unconnected-(U3-PB12-Pad17)") (class "Default")
      (node (ref "U3") (pin "17") (pinfunction "PB12_17") (pintype "bidirectional"))
    )
    (net (code "91") (name "unconnected-(U3-PB13-Pad16)") (class "Default")
      (node (ref "U3") (pin "16") (pinfunction "PB13_16") (pintype "bidirectional"))
    )
    (net (code "92") (name "unconnected-(U3-PB14-Pad15)") (class "Default")
      (node (ref "U3") (pin "15") (pinfunction "PB14_15") (pintype "bidirectional"))
    )
    (net (code "93") (name "unconnected-(U3-PB15-Pad14)") (class "Default")
      (node (ref "U3") (pin "14") (pinfunction "PB15_14") (pintype "bidirectional"))
    )
    (net (code "94") (name "unconnected-(U3-PH0-OSC_IN-Pad46)") (class "Default")
      (node (ref "U3") (pin "46") (pinfunction "PH0-OSC_IN_46") (pintype "bidirectional"))
    )
    (net (code "95") (name "unconnected-(U3-PH1-OSC_OUT-Pad45)") (class "Default")
      (node (ref "U3") (pin "45") (pinfunction "PH1-OSC_OUT_45") (pintype "bidirectional"))
    )
    (net (code "96") (name "unconnected-(U3-STSAFE_NRST-Pad31)") (class "Default")
      (node (ref "U3") (pin "31") (pinfunction "STSAFE_NRST_31") (pintype "bidirectional"))
    )
    (net (code "97") (name "unconnected-(U3-SWCLK-Pad42)") (class "Default")
      (node (ref "U3") (pin "42") (pinfunction "SWCLK_42") (pintype "bidirectional"))
    )
    (net (code "98") (name "unconnected-(U3-SWDIO-Pad41)") (class "Default")
      (node (ref "U3") (pin "41") (pinfunction "SWDIO_41") (pintype "bidirectional"))
    )
    (net (code "99") (name "unconnected-(U3-SX1276_DIO4-Pad10)") (class "Default")
      (node (ref "U3") (pin "10") (pinfunction "SX1276_DIO4_10") (pintype "bidirectional"))
    )
    (net (code "100") (name "unconnected-(U3-TCXO_OUT-Pad47)") (class "Default")
      (node (ref "U3") (pin "47") (pinfunction "TCXO_OUT_47") (pintype "bidirectional"))
    )
    (net (code "101") (name "unconnected-(U3-VDD_TCXO-Pad48)") (class "Default")
      (node (ref "U3") (pin "48") (pinfunction "VDD_TCXO_48") (pintype "bidirectional"))
    )
    (net (code "102") (name "unconnected-(U3-VDD_USB-Pad4)") (class "Default")
      (node (ref "U3") (pin "4") (pinfunction "VDD_USB_4") (pintype "bidirectional"))
    )
  )
)
